# Dimmer.net
KiCad netlist of a schematic drawn in EAGLE
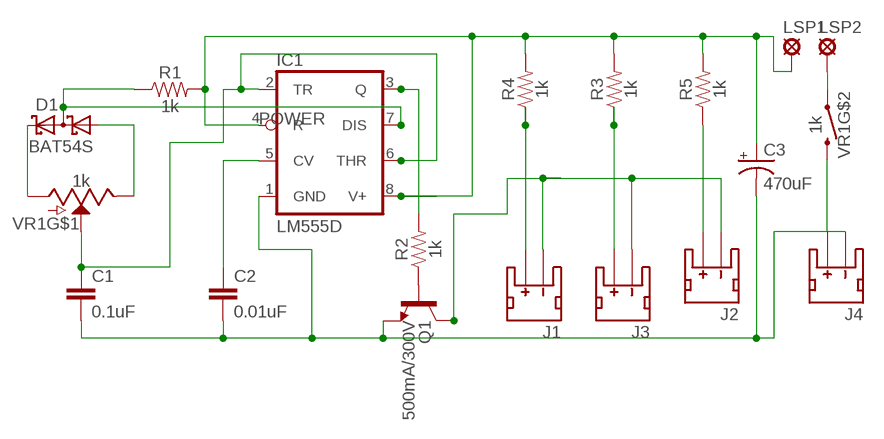
[diagram p0: schematic, sheet 1]

(export (version "E")
  (design (tool "Eeschema 10.0.6"))
  (components
    (comp (ref "C1")
      (value "0.1uF")
      (footprint "eagle-import:C0805")
      (libsource (lib "eagle-import") (part "C"))
    )
    (comp (ref "C2")
      (value "0.01uF")
      (footprint "eagle-import:C0402")
      (libsource (lib "eagle-import") (part "CC0402"))
    )
    (comp (ref "C3")
      (value "470uF")
      (footprint "eagle-import:085CS_1AW")
      (libsource (lib "eagle-import") (part "CPOL-US085CS-1AW"))
    )
    (comp (ref "D1")
      (value "BAT54S")
      (footprint "eagle-import:SOT23")
      (libsource (lib "eagle-import") (part "BAT54S"))
    )
    (comp (ref "IC1")
      (value "LM555D")
      (footprint "eagle-import:SO08")
      (libsource (lib "eagle-import") (part "555DLM"))
    )
    (comp (ref "J1")
      (value "JST_2MM_MALE")
      (footprint "eagle-import:JST-2-SMD")
      (libsource (lib "eagle-import") (part "JST_2MM_MALE"))
    )
    (comp (ref "J2")
      (value "JST_2MM_MALE")
      (footprint "eagle-import:JST-2-SMD")
      (libsource (lib "eagle-import") (part "JST_2MM_MALE"))
    )
    (comp (ref "J3")
      (value "JST_2MM_MALE")
      (footprint "eagle-import:JST-2-SMD")
      (libsource (lib "eagle-import") (part "JST_2MM_MALE"))
    )
    (comp (ref "J4")
      (value "JST_2MM_MALE")
      (footprint "eagle-import:JST-2-SMD")
      (libsource (lib "eagle-import") (part "JST_2MM_MALE"))
    )
    (comp (ref "LSP1")
      (value "LSP10")
      (footprint "eagle-import:LSP10")
      (libsource (lib "eagle-import") (part "LSP10"))
    )
    (comp (ref "LSP2")
      (value "LSP10")
      (footprint "eagle-import:LSP10")
      (libsource (lib "eagle-import") (part "LSP10"))
    )
    (comp (ref "Q1")
      (value "500mA/300V")
      (footprint "eagle-import:SOT23-3")
      (libsource (lib "eagle-import") (part "TRANS_NPN-MMBTA42"))
    )
    (comp (ref "R1")
      (value "1k")
      (footprint "eagle-import:0603")
      (libsource (lib "eagle-import") (part "1KOHM-0603-1/10W-1%"))
    )
    (comp (ref "R2")
      (value "1k")
      (footprint "eagle-import:0603")
      (libsource (lib "eagle-import") (part "1KOHM-0603-1/10W-1%"))
    )
    (comp (ref "R3")
      (value "1k")
      (footprint "eagle-import:0603")
      (libsource (lib "eagle-import") (part "1KOHM-0603-1/10W-1%"))
    )
    (comp (ref "R4")
      (value "1k")
      (footprint "eagle-import:0603")
      (libsource (lib "eagle-import") (part "1KOHM-0603-1/10W-1%"))
    )
    (comp (ref "R5")
      (value "1k")
      (footprint "eagle-import:0603")
      (libsource (lib "eagle-import") (part "1KOHM-0603-1/10W-1%"))
    )
    (comp (ref "VR1")
      (value "1k")
      (footprint "eagle-import:POT-SWITCH-PTH")
      (libsource (lib "eagle-import") (part "POTENTIOMETER_W/SWITCHPOT_PTH_SWITCH"))
    )
  )
  (nets
    (net (code "1") (name "/POWER") (class "Default")
      (node (ref "C3") (pin "+") (pinfunction "+_+") (pintype "passive"))
      (node (ref "IC1") (pin "4") (pinfunction "R_4") (pintype "input"))
      (node (ref "IC1") (pin "8") (pinfunction "V+_8") (pintype "power_in"))
      (node (ref "LSP1") (pin "MP") (pinfunction "MP_MP") (pintype "passive"))
      (node (ref "R1") (pin "2") (pinfunction "2_2") (pintype "passive"))
      (node (ref "R3") (pin "2") (pinfunction "2_2") (pintype "passive"))
      (node (ref "R4") (pin "2") (pinfunction "2_2") (pintype "passive"))
      (node (ref "R5") (pin "2") (pinfunction "2_2") (pintype "passive"))
    )
    (net (code "2") (name "Net-(D1-A1)") (class "Default")
      (node (ref "D1") (pin "1") (pinfunction "A1_1") (pintype "passive"))
      (node (ref "VR1") (pin "3") (pinfunction "E_3") (pintype "passive"))
    )
    (net (code "3") (name "Net-(D1-C1A2)") (class "Default")
      (node (ref "D1") (pin "3") (pinfunction "C1A2_3") (pintype "passive"))
      (node (ref "IC1") (pin "7") (pinfunction "DIS_7") (pintype "input"))
      (node (ref "R1") (pin "1") (pinfunction "1_1") (pintype "passive"))
    )
    (net (code "4") (name "Net-(D1-C2)") (class "Default")
      (node (ref "D1") (pin "2") (pinfunction "C2_2") (pintype "passive"))
      (node (ref "VR1") (pin "1") (pinfunction "A_1") (pintype "passive"))
    )
    (net (code "5") (name "Net-(IC1-CV)") (class "Default")
      (node (ref "C2") (pin "1") (pinfunction "1_1") (pintype "passive"))
      (node (ref "IC1") (pin "5") (pinfunction "CV_5") (pintype "input"))
    )
    (net (code "6") (name "Net-(IC1-GND)") (class "Default")
      (node (ref "C1") (pin "2") (pinfunction "2_2") (pintype "passive"))
      (node (ref "C2") (pin "2") (pinfunction "2_2") (pintype "passive"))
      (node (ref "C3") (pin "-") (pinfunction "-_-") (pintype "passive"))
      (node (ref "IC1") (pin "1") (pinfunction "GND_1") (pintype "power_in"))
      (node (ref "J4") (pin "1") (pinfunction "-_1") (pintype "bidirectional"))
      (node (ref "Q1") (pin "2") (pinfunction "E_2") (pintype "passive"))
    )
    (net (code "7") (name "Net-(IC1-Q)") (class "Default")
      (node (ref "IC1") (pin "3") (pinfunction "Q_3") (pintype "output"))
      (node (ref "R2") (pin "2") (pinfunction "2_2") (pintype "passive"))
    )
    (net (code "8") (name "Net-(IC1-THR)") (class "Default")
      (node (ref "C1") (pin "1") (pinfunction "1_1") (pintype "passive"))
      (node (ref "IC1") (pin "2") (pinfunction "TR_2") (pintype "input"))
      (node (ref "IC1") (pin "6") (pinfunction "THR_6") (pintype "input"))
      (node (ref "VR1") (pin "2") (pinfunction "S_2") (pintype "passive"))
    )
    (net (code "9") (name "Net-(J1-+)") (class "Default")
      (node (ref "J1") (pin "2") (pinfunction "+_2") (pintype "bidirectional"))
      (node (ref "R4") (pin "1") (pinfunction "1_1") (pintype "passive"))
    )
    (net (code "10") (name "Net-(J1--)") (class "Default")
      (node (ref "J1") (pin "1") (pinfunction "-_1") (pintype "bidirectional"))
      (node (ref "J2") (pin "1") (pinfunction "-_1") (pintype "bidirectional"))
      (node (ref "J3") (pin "1") (pinfunction "-_1") (pintype "bidirectional"))
      (node (ref "Q1") (pin "3") (pinfunction "C_3") (pintype "passive"))
    )
    (net (code "11") (name "Net-(J2-+)") (class "Default")
      (node (ref "J2") (pin "2") (pinfunction "+_2") (pintype "bidirectional"))
      (node (ref "R5") (pin "1") (pinfunction "1_1") (pintype "passive"))
    )
    (net (code "12") (name "Net-(J3-+)") (class "Default")
      (node (ref "J3") (pin "2") (pinfunction "+_2") (pintype "bidirectional"))
      (node (ref "R3") (pin "1") (pinfunction "1_1") (pintype "passive"))
    )
    (net (code "13") (name "Net-(J4-+)") (class "Default")
      (node (ref "J4") (pin "2") (pinfunction "+_2") (pintype "bidirectional"))
      (node (ref "VR1") (pin "S2") (pinfunction "2_S2") (pintype "passive"))
    )
    (net (code "14") (name "Net-(Q1-B)") (class "Default")
      (node (ref "Q1") (pin "1") (pinfunction "B_1") (pintype "passive"))
      (node (ref "R2") (pin "1") (pinfunction "1_1") (pintype "passive"))
    )
    (net (code "15") (name "Net-(VR1B-1)") (class "Default")
      (node (ref "LSP2") (pin "MP") (pinfunction "MP_MP") (pintype "passive"))
      (node (ref "VR1") (pin "S1") (pinfunction "1_S1") (pintype "passive"))
    )
    (net (code "16") (name "unconnected-(J1-PAD1-PadNC1)") (class "Default")
      (node (ref "J1") (pin "NC1") (pinfunction "PAD1_NC1") (pintype "bidirectional"))
    )
    (net (code "17") (name "unconnected-(J1-PAD2-PadNC2)") (class "Default")
      (node (ref "J1") (pin "NC2") (pinfunction "PAD2_NC2") (pintype "bidirectional"))
    )
    (net (code "18") (name "unconnected-(J2-PAD1-PadNC1)") (class "Default")
      (node (ref "J2") (pin "NC1") (pinfunction "PAD1_NC1") (pintype "bidirectional"))
    )
    (net (code "19") (name "unconnected-(J2-PAD2-PadNC2)") (class "Default")
      (node (ref "J2") (pin "NC2") (pinfunction "PAD2_NC2") (pintype "bidirectional"))
    )
    (net (code "20") (name "unconnected-(J3-PAD1-PadNC1)") (class "Default")
      (node (ref "J3") (pin "NC1") (pinfunction "PAD1_NC1") (pintype "bidirectional"))
    )
    (net (code "21") (name "unconnected-(J3-PAD2-PadNC2)") (class "Default")
      (node (ref "J3") (pin "NC2") (pinfunction "PAD2_NC2") (pintype "bidirectional"))
    )
    (net (code "22") (name "unconnected-(J4-PAD1-PadNC1)") (class "Default")
      (node (ref "J4") (pin "NC1") (pinfunction "PAD1_NC1") (pintype "bidirectional"))
    )
    (net (code "23") (name "unconnected-(J4-PAD2-PadNC2)") (class "Default")
      (node (ref "J4") (pin "NC2") (pinfunction "PAD2_NC2") (pintype "bidirectional"))
    )
  )
)
